# mainodzysk2.net
KiCad netlist of a schematic drawn in EAGLE
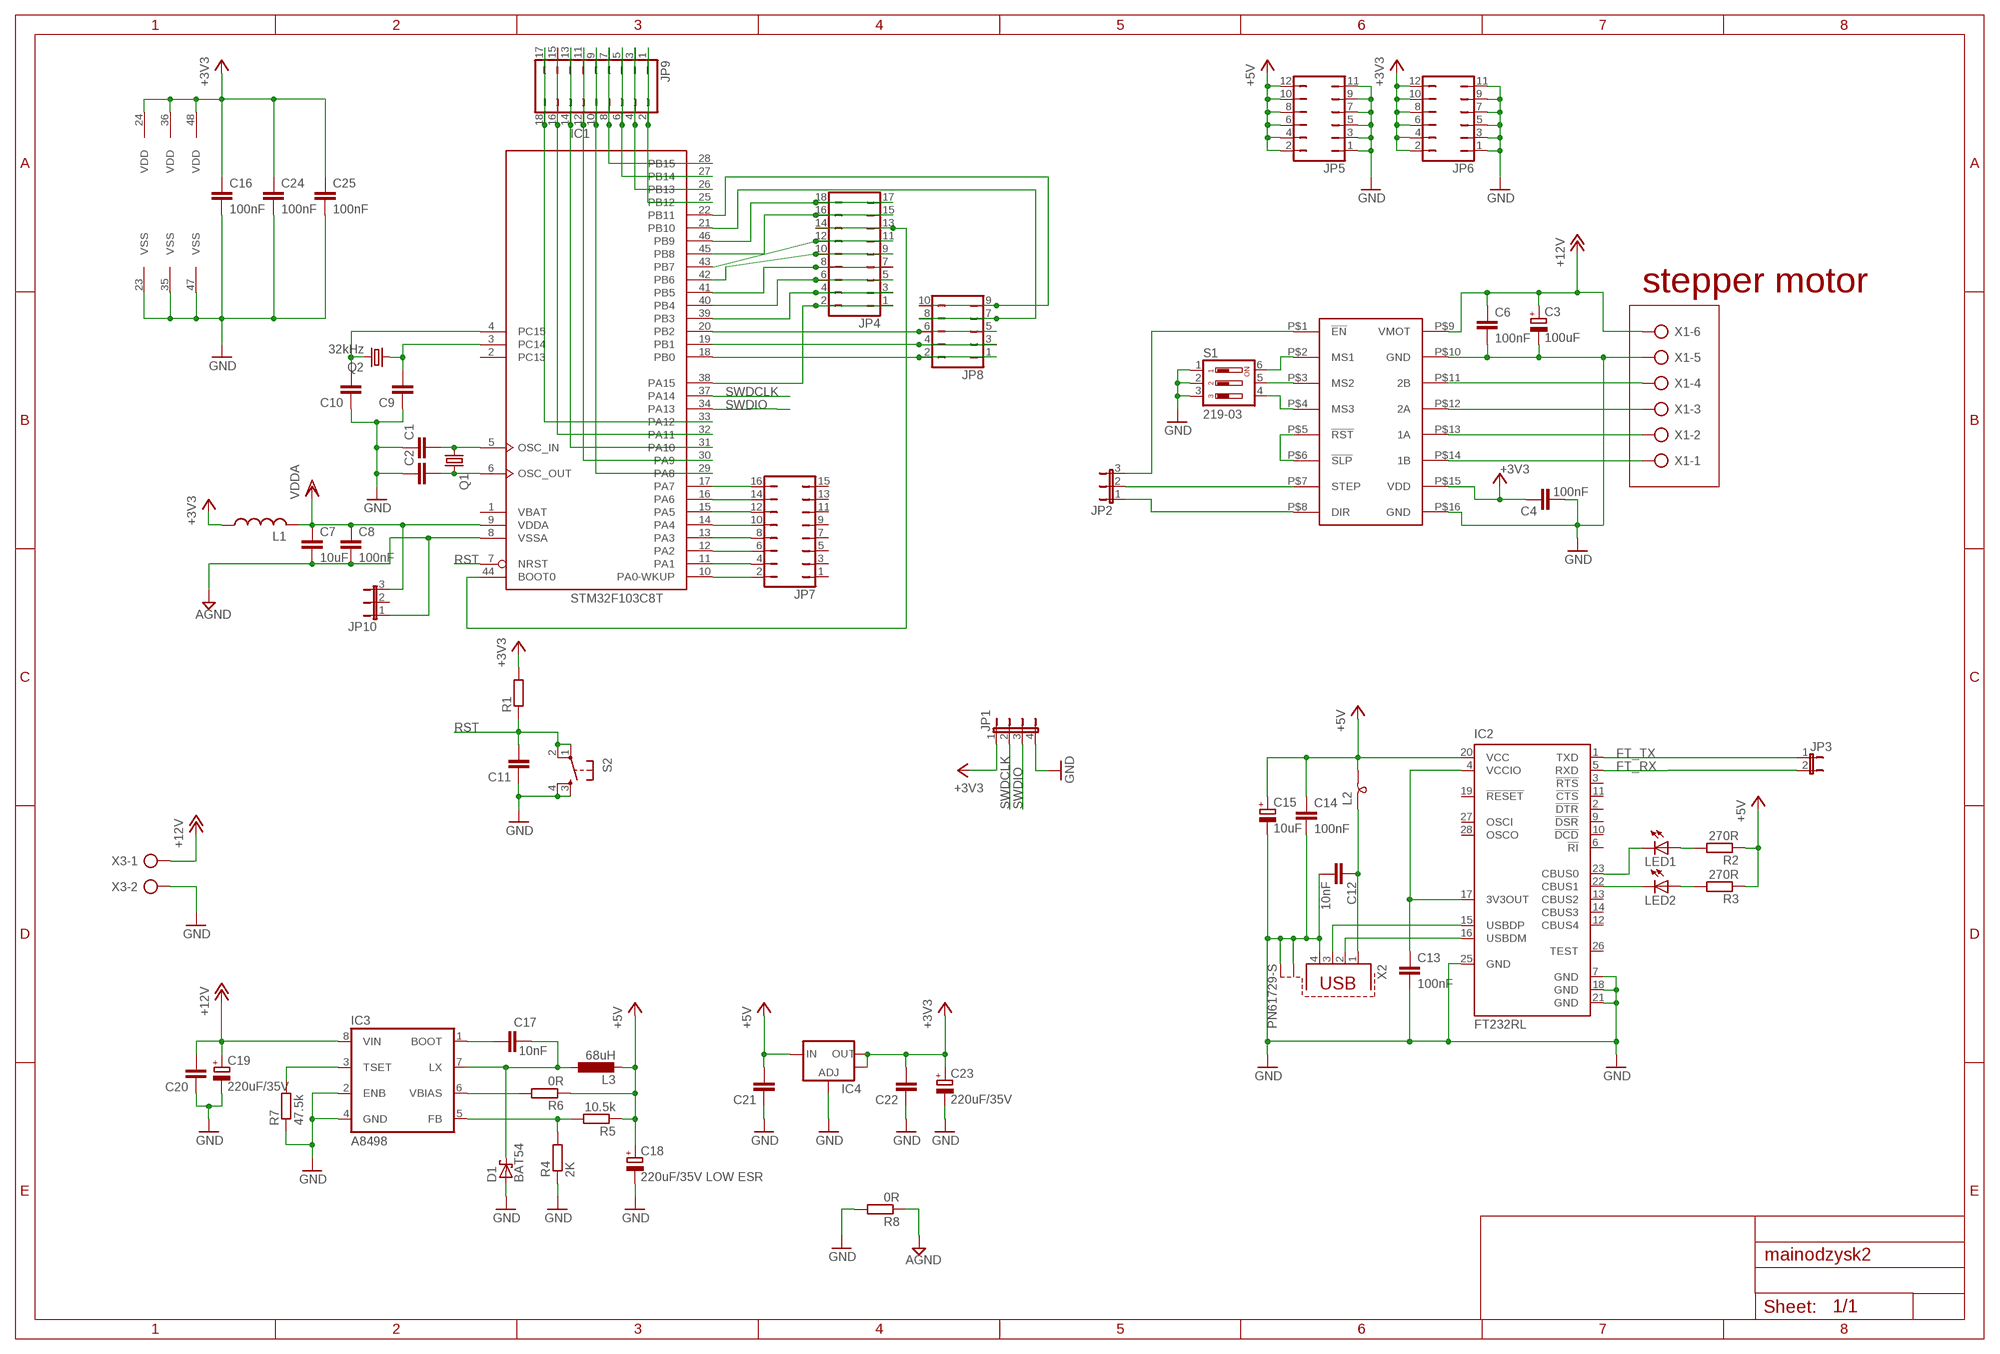
[diagram p0: schematic, sheet 1]

(export (version "E")
  (design (tool "Eeschema 10.0.6"))
  (components
    (comp (ref "C1")
      (value "C-EUC0603K")
      (footprint "eagle-import:C0603K")
      (libsource (lib "eagle-import") (part "C-EUC0603K"))
    )
    (comp (ref "C2")
      (value "C-EUC0603K")
      (footprint "eagle-import:C0603K")
      (libsource (lib "eagle-import") (part "C-EUC0603K"))
    )
    (comp (ref "C3")
      (value "100uF")
      (footprint "eagle-import:E5-10,5")
      (libsource (lib "eagle-import") (part "CPOL-EUE5-10.5"))
    )
    (comp (ref "C4")
      (value "100nF")
      (footprint "eagle-import:C0603K")
      (libsource (lib "eagle-import") (part "C-EUC0603K"))
    )
    (comp (ref "C6")
      (value "100nF")
      (footprint "eagle-import:C0603K")
      (libsource (lib "eagle-import") (part "C-EUC0603K"))
    )
    (comp (ref "C7")
      (value "10uF")
      (footprint "eagle-import:C1812")
      (libsource (lib "eagle-import") (part "C-EUC1812"))
    )
    (comp (ref "C8")
      (value "100nF")
      (footprint "eagle-import:C0603K")
      (libsource (lib "eagle-import") (part "C-EUC0603K"))
    )
    (comp (ref "C9")
      (value "C-EUC0603K")
      (footprint "eagle-import:C0603K")
      (libsource (lib "eagle-import") (part "C-EUC0603K"))
    )
    (comp (ref "C10")
      (value "C-EUC0603K")
      (footprint "eagle-import:C0603K")
      (libsource (lib "eagle-import") (part "C-EUC0603K"))
    )
    (comp (ref "C11")
      (value "C-EUC0603K")
      (footprint "eagle-import:C0603K")
      (libsource (lib "eagle-import") (part "C-EUC0603K"))
    )
    (comp (ref "C12")
      (value "10nF")
      (footprint "eagle-import:C0603K")
      (libsource (lib "eagle-import") (part "C-EUC0603K"))
    )
    (comp (ref "C13")
      (value "100nF")
      (footprint "eagle-import:C0603K")
      (libsource (lib "eagle-import") (part "C-EUC0603K"))
    )
    (comp (ref "C14")
      (value "100nF")
      (footprint "eagle-import:C0603K")
      (libsource (lib "eagle-import") (part "C-EUC0603K"))
    )
    (comp (ref "C15")
      (value "10uF")
      (footprint "eagle-import:E5-10,5")
      (libsource (lib "eagle-import") (part "CPOL-EUE5-10.5"))
    )
    (comp (ref "C16")
      (value "100nF")
      (footprint "eagle-import:C025-025X050")
      (libsource (lib "eagle-import") (part "C-EU025-025X050"))
    )
    (comp (ref "C17")
      (value "10nF")
      (footprint "eagle-import:C050-030X075")
      (libsource (lib "eagle-import") (part "C-EU050-030X075"))
    )
    (comp (ref "C18")
      (value "220uF/35V LOW ESR")
      (footprint "eagle-import:E5-10,5")
      (libsource (lib "eagle-import") (part "CPOL-EUE5-10.5"))
    )
    (comp (ref "C19")
      (value "220uF/35V")
      (footprint "eagle-import:E5-10,5")
      (libsource (lib "eagle-import") (part "CPOL-EUE5-10.5"))
    )
    (comp (ref "C20")
      (value "C-EUC0603K")
      (footprint "eagle-import:C0603K")
      (libsource (lib "eagle-import") (part "C-EUC0603K"))
    )
    (comp (ref "C21")
      (value "C-EUC0603K")
      (footprint "eagle-import:C0603K")
      (libsource (lib "eagle-import") (part "C-EUC0603K"))
    )
    (comp (ref "C22")
      (value "C-EUC0603K")
      (footprint "eagle-import:C0603K")
      (libsource (lib "eagle-import") (part "C-EUC0603K"))
    )
    (comp (ref "C23")
      (value "220uF/35V")
      (footprint "eagle-import:E5-10,5")
      (libsource (lib "eagle-import") (part "CPOL-EUE5-10.5"))
    )
    (comp (ref "C24")
      (value "100nF")
      (footprint "eagle-import:C0603K")
      (libsource (lib "eagle-import") (part "C-EUC0603K"))
    )
    (comp (ref "C25")
      (value "100nF")
      (footprint "eagle-import:C025-024X044")
      (libsource (lib "eagle-import") (part "C-EU025-024X044"))
    )
    (comp (ref "D1")
      (value "BAT54")
      (footprint "eagle-import:SOT23")
      (libsource (lib "eagle-import") (part "BAT54"))
    )
    (comp (ref "IC1")
      (value "STM32F103C8T")
      (footprint "eagle-import:LQFP48")
      (libsource (lib "eagle-import") (part "STM32F103CT8"))
    )
    (comp (ref "IC2")
      (value "FT232RL")
      (footprint "eagle-import:SSOP28")
      (libsource (lib "eagle-import") (part "FT232RL"))
    )
    (comp (ref "IC3")
      (value "A8498")
      (footprint "eagle-import:SO08")
      (libsource (lib "eagle-import") (part "A8498"))
    )
    (comp (ref "IC4")
      (value "V_REG_LM1117SOT223")
      (footprint "eagle-import:SOT223")
      (libsource (lib "eagle-import") (part "V_REG_LM1117SOT223"))
    )
    (comp (ref "JP1")
      (value "JP4E")
      (footprint "eagle-import:JP4")
      (libsource (lib "eagle-import") (part "JP4E"))
    )
    (comp (ref "JP2")
      (value "JP2E")
      (footprint "eagle-import:JP2")
      (libsource (lib "eagle-import") (part "JP2E"))
    )
    (comp (ref "JP3")
      (value "JP1E")
      (footprint "eagle-import:JP1")
      (libsource (lib "eagle-import") (part "JP1E"))
    )
    (comp (ref "JP4")
      (value "JP9Q")
      (footprint "eagle-import:JP9Q")
      (libsource (lib "eagle-import") (part "JP9Q"))
    )
    (comp (ref "JP5")
      (value "JP6Q")
      (footprint "eagle-import:JP6Q")
      (libsource (lib "eagle-import") (part "JP6Q"))
    )
    (comp (ref "JP6")
      (value "JP6Q")
      (footprint "eagle-import:JP6Q")
      (libsource (lib "eagle-import") (part "JP6Q"))
    )
    (comp (ref "JP7")
      (value "JP8Q")
      (footprint "eagle-import:JP8Q")
      (libsource (lib "eagle-import") (part "JP8Q"))
    )
    (comp (ref "JP8")
      (value "JP5Q")
      (footprint "eagle-import:JP5Q")
      (libsource (lib "eagle-import") (part "JP5Q"))
    )
    (comp (ref "JP9")
      (value "JP9Q")
      (footprint "eagle-import:JP9Q")
      (libsource (lib "eagle-import") (part "JP9Q"))
    )
    (comp (ref "JP10")
      (value "JP2W")
      (footprint "eagle-import:JP2W")
      (libsource (lib "eagle-import") (part "JP2W"))
    )
    (comp (ref "L1")
      (value "L-USL2012C")
      (footprint "eagle-import:L2012C")
      (libsource (lib "eagle-import") (part "L-USL2012C"))
    )
    (comp (ref "L2")
      (value "SM-B5")
      (footprint "eagle-import:SM-B5")
      (libsource (lib "eagle-import") (part "SM-B5"))
    )
    (comp (ref "L3")
      (value "68uH")
      (footprint "eagle-import:PIS2816")
      (libsource (lib "eagle-import") (part "L-EUPIS2816"))
    )
    (comp (ref "LED1")
      (value "LEDCHIPLED_0805")
      (footprint "eagle-import:CHIPLED_0805")
      (libsource (lib "eagle-import") (part "LEDCHIPLED_0805"))
    )
    (comp (ref "LED2")
      (value "LEDCHIPLED_0805")
      (footprint "eagle-import:CHIPLED_0805")
      (libsource (lib "eagle-import") (part "LEDCHIPLED_0805"))
    )
    (comp (ref "Q1")
      (value "CRYSTALHC49UP")
      (footprint "eagle-import:HC49UP")
      (libsource (lib "eagle-import") (part "CRYSTALHC49UP"))
    )
    (comp (ref "Q2")
      (value "32kHz")
      (footprint "eagle-import:TC26H")
      (libsource (lib "eagle-import") (part "CRYSTALTC26H"))
    )
    (comp (ref "R1")
      (value "R-EU_R0805")
      (footprint "eagle-import:R0805")
      (libsource (lib "eagle-import") (part "R-EU_R0805"))
    )
    (comp (ref "R2")
      (value "270R")
      (footprint "eagle-import:R0805")
      (libsource (lib "eagle-import") (part "R-EU_R0805"))
    )
    (comp (ref "R3")
      (value "270R")
      (footprint "eagle-import:R0805")
      (libsource (lib "eagle-import") (part "R-EU_R0805"))
    )
    (comp (ref "R4")
      (value "2K")
      (footprint "eagle-import:0207_12")
      (libsource (lib "eagle-import") (part "R-EU_0207/12"))
    )
    (comp (ref "R5")
      (value "10.5k")
      (footprint "eagle-import:R0805")
      (libsource (lib "eagle-import") (part "R-EU_R0805"))
    )
    (comp (ref "R6")
      (value "0R")
      (footprint "eagle-import:R0805")
      (libsource (lib "eagle-import") (part "R-EU_R0805"))
    )
    (comp (ref "R7")
      (value "47.5k")
      (footprint "eagle-import:R0805")
      (libsource (lib "eagle-import") (part "R-EU_R0805"))
    )
    (comp (ref "R8")
      (value "0R")
      (footprint "eagle-import:0207_10")
      (libsource (lib "eagle-import") (part "R-EU_0207/10"))
    )
    (comp (ref "S1")
      (value "219-03")
      (footprint "eagle-import:CTS-219-03")
      (libsource (lib "eagle-import") (part "219-03"))
    )
    (comp (ref "S2")
      (value "TAC_SWITCHPTH")
      (footprint "eagle-import:TACTILE-PTH")
      (libsource (lib "eagle-import") (part "TAC_SWITCHPTH"))
    )
    (comp (ref "U$1")
      (value "A4988_POLOLU_STEPER_MOTOR")
      (footprint "eagle-import:6X8")
      (libsource (lib "eagle-import") (part "A4988_POLOLU_STEPER_MOTOR"))
    )
    (comp (ref "X1")
      (value "AK300/6")
      (footprint "eagle-import:AK300_6")
      (libsource (lib "eagle-import") (part "AK300/6"))
    )
    (comp (ref "X2")
      (value "PN61729-S")
      (footprint "eagle-import:PN61729-S")
      (libsource (lib "eagle-import") (part "PN61729-S"))
    )
    (comp (ref "X3")
      (value "AK300/2")
      (footprint "eagle-import:AK300_2")
      (libsource (lib "eagle-import") (part "AK300/2"))
    )
  )
  (nets
    (net (code "1") (name "+3V3") (class "Default")
      (node (ref "C16") (pin "1") (pinfunction "1_1") (pintype "passive"))
      (node (ref "C22") (pin "2") (pinfunction "2_2") (pintype "passive"))
      (node (ref "C23") (pin "+") (pinfunction "+_+") (pintype "passive"))
      (node (ref "C24") (pin "1") (pinfunction "1_1") (pintype "passive"))
      (node (ref "C25") (pin "1") (pinfunction "1_1") (pintype "passive"))
      (node (ref "C4") (pin "1") (pinfunction "1_1") (pintype "passive"))
      (node (ref "IC1") (pin "24") (pinfunction "VDD_24") (pintype "power_in"))
      (node (ref "IC1") (pin "36") (pinfunction "VDD_36") (pintype "power_in"))
      (node (ref "IC1") (pin "48") (pinfunction "VDD_48") (pintype "power_in"))
      (node (ref "IC4") (pin "2") (pinfunction "OUT_2") (pintype "output"))
      (node (ref "IC4") (pin "4") (pinfunction "OUT_4") (pintype "output"))
      (node (ref "JP1") (pin "1") (pinfunction "1_1") (pintype "passive"))
      (node (ref "JP6") (pin "10") (pinfunction "10_10") (pintype "passive"))
      (node (ref "JP6") (pin "12") (pinfunction "12_12") (pintype "passive"))
      (node (ref "JP6") (pin "2") (pinfunction "2_2") (pintype "passive"))
      (node (ref "JP6") (pin "4") (pinfunction "4_4") (pintype "passive"))
      (node (ref "JP6") (pin "6") (pinfunction "6_6") (pintype "passive"))
      (node (ref "JP6") (pin "8") (pinfunction "8_8") (pintype "passive"))
      (node (ref "L1") (pin "1") (pinfunction "1_1") (pintype "passive"))
      (node (ref "R1") (pin "2") (pinfunction "2_2") (pintype "passive"))
      (node (ref "U$1") (pin "P$15") (pinfunction "VDD_P$15") (pintype "bidirectional"))
    )
    (net (code "2") (name "+5V") (class "Default")
      (node (ref "C14") (pin "1") (pinfunction "1_1") (pintype "passive"))
      (node (ref "C15") (pin "+") (pinfunction "+_+") (pintype "passive"))
      (node (ref "C18") (pin "+") (pinfunction "+_+") (pintype "passive"))
      (node (ref "C21") (pin "2") (pinfunction "2_2") (pintype "passive"))
      (node (ref "IC2") (pin "20") (pinfunction "VCC_20") (pintype "power_in"))
      (node (ref "IC4") (pin "3") (pinfunction "IN_3") (pintype "input"))
      (node (ref "JP5") (pin "10") (pinfunction "10_10") (pintype "passive"))
      (node (ref "JP5") (pin "12") (pinfunction "12_12") (pintype "passive"))
      (node (ref "JP5") (pin "2") (pinfunction "2_2") (pintype "passive"))
      (node (ref "JP5") (pin "4") (pinfunction "4_4") (pintype "passive"))
      (node (ref "JP5") (pin "6") (pinfunction "6_6") (pintype "passive"))
      (node (ref "JP5") (pin "8") (pinfunction "8_8") (pintype "passive"))
      (node (ref "L2") (pin "2") (pinfunction "2_2") (pintype "passive"))
      (node (ref "L3") (pin "2") (pinfunction "2_2") (pintype "passive"))
      (node (ref "R2") (pin "1") (pinfunction "1_1") (pintype "passive"))
      (node (ref "R3") (pin "1") (pinfunction "1_1") (pintype "passive"))
      (node (ref "R5") (pin "1") (pinfunction "1_1") (pintype "passive"))
      (node (ref "R6") (pin "1") (pinfunction "1_1") (pintype "passive"))
    )
    (net (code "3") (name "+12V") (class "Default")
      (node (ref "C19") (pin "+") (pinfunction "+_+") (pintype "passive"))
      (node (ref "C20") (pin "2") (pinfunction "2_2") (pintype "passive"))
      (node (ref "C3") (pin "+") (pinfunction "+_+") (pintype "passive"))
      (node (ref "C6") (pin "1") (pinfunction "1_1") (pintype "passive"))
      (node (ref "IC3") (pin "8") (pinfunction "VIN_8") (pintype "input"))
      (node (ref "U$1") (pin "P$9") (pinfunction "VMOT_P$9") (pintype "bidirectional"))
      (node (ref "X1") (pin "6") (pinfunction "KL_6") (pintype "passive"))
      (node (ref "X3") (pin "1") (pinfunction "KL_1") (pintype "passive"))
    )
    (net (code "4") (name "/FT_RX") (class "Default")
      (node (ref "IC2") (pin "5") (pinfunction "RXD_5") (pintype "input"))
      (node (ref "JP3") (pin "2") (pinfunction "2_2") (pintype "passive"))
    )
    (net (code "5") (name "/FT_TX") (class "Default")
      (node (ref "IC2") (pin "1") (pinfunction "TXD_1") (pintype "output"))
      (node (ref "JP3") (pin "1") (pinfunction "1_1") (pintype "passive"))
    )
    (net (code "6") (name "/RST") (class "Default")
      (node (ref "C11") (pin "2") (pinfunction "2_2") (pintype "passive"))
      (node (ref "IC1") (pin "7") (pinfunction "NRST_7") (pintype "bidirectional"))
      (node (ref "R1") (pin "1") (pinfunction "1_1") (pintype "passive"))
      (node (ref "S2") (pin "1") (pinfunction "1_1") (pintype "passive"))
      (node (ref "S2") (pin "2") (pinfunction "2_2") (pintype "passive"))
    )
    (net (code "7") (name "/SWDCLK") (class "Default")
      (node (ref "IC1") (pin "37") (pinfunction "PA14_37") (pintype "bidirectional"))
      (node (ref "JP1") (pin "2") (pinfunction "2_2") (pintype "passive"))
    )
    (net (code "8") (name "/SWDIO") (class "Default")
      (node (ref "IC1") (pin "34") (pinfunction "PA13_34") (pintype "bidirectional"))
      (node (ref "JP1") (pin "3") (pinfunction "3_3") (pintype "passive"))
    )
    (net (code "9") (name "/VBAT") (class "Default")
      (node (ref "IC1") (pin "1") (pinfunction "VBAT_1") (pintype "power_in"))
    )
    (net (code "10") (name "AGND") (class "Default")
      (node (ref "C7") (pin "2") (pinfunction "2_2") (pintype "passive"))
      (node (ref "C8") (pin "2") (pinfunction "2_2") (pintype "passive"))
      (node (ref "IC1") (pin "8") (pinfunction "VSSA_8") (pintype "power_in"))
      (node (ref "JP10") (pin "1") (pinfunction "1_1") (pintype "passive"))
      (node (ref "R8") (pin "1") (pinfunction "1_1") (pintype "passive"))
    )
    (net (code "11") (name "GND") (class "Default")
      (node (ref "C1") (pin "1") (pinfunction "1_1") (pintype "passive"))
      (node (ref "C10") (pin "1") (pinfunction "1_1") (pintype "passive"))
      (node (ref "C11") (pin "1") (pinfunction "1_1") (pintype "passive"))
      (node (ref "C12") (pin "2") (pinfunction "2_2") (pintype "passive"))
      (node (ref "C13") (pin "2") (pinfunction "2_2") (pintype "passive"))
      (node (ref "C14") (pin "2") (pinfunction "2_2") (pintype "passive"))
      (node (ref "C15") (pin "-") (pinfunction "-_-") (pintype "passive"))
      (node (ref "C16") (pin "2") (pinfunction "2_2") (pintype "passive"))
      (node (ref "C18") (pin "-") (pinfunction "-_-") (pintype "passive"))
      (node (ref "C19") (pin "-") (pinfunction "-_-") (pintype "passive"))
      (node (ref "C2") (pin "1") (pinfunction "1_1") (pintype "passive"))
      (node (ref "C20") (pin "1") (pinfunction "1_1") (pintype "passive"))
      (node (ref "C21") (pin "1") (pinfunction "1_1") (pintype "passive"))
      (node (ref "C22") (pin "1") (pinfunction "1_1") (pintype "passive"))
      (node (ref "C23") (pin "-") (pinfunction "-_-") (pintype "passive"))
      (node (ref "C24") (pin "2") (pinfunction "2_2") (pintype "passive"))
      (node (ref "C25") (pin "2") (pinfunction "2_2") (pintype "passive"))
      (node (ref "C3") (pin "-") (pinfunction "-_-") (pintype "passive"))
      (node (ref "C4") (pin "2") (pinfunction "2_2") (pintype "passive"))
      (node (ref "C6") (pin "2") (pinfunction "2_2") (pintype "passive"))
      (node (ref "C9") (pin "1") (pinfunction "1_1") (pintype "passive"))
      (node (ref "D1") (pin "1") (pinfunction "A_1") (pintype "passive"))
      (node (ref "IC1") (pin "23") (pinfunction "VSS_23") (pintype "power_in"))
      (node (ref "IC1") (pin "35") (pinfunction "VSS_35") (pintype "power_in"))
      (node (ref "IC1") (pin "47") (pinfunction "VSS_47") (pintype "power_in"))
      (node (ref "IC2") (pin "18") (pinfunction "GND_18") (pintype "power_in"))
      (node (ref "IC2") (pin "21") (pinfunction "GND_21") (pintype "power_in"))
      (node (ref "IC2") (pin "25") (pinfunction "GND_25") (pintype "power_in"))
      (node (ref "IC2") (pin "7") (pinfunction "GND_7") (pintype "power_in"))
      (node (ref "IC3") (pin "2") (pinfunction "ENB_2") (pintype "input"))
      (node (ref "IC3") (pin "4") (pinfunction "GND_4") (pintype "power_in"))
      (node (ref "IC4") (pin "1") (pinfunction "ADJ_1") (pintype "input"))
      (node (ref "JP1") (pin "4") (pinfunction "4_4") (pintype "passive"))
      (node (ref "JP5") (pin "1") (pinfunction "1_1") (pintype "passive"))
      (node (ref "JP5") (pin "11") (pinfunction "11_11") (pintype "passive"))
      (node (ref "JP5") (pin "3") (pinfunction "3_3") (pintype "passive"))
      (node (ref "JP5") (pin "5") (pinfunction "5_5") (pintype "passive"))
      (node (ref "JP5") (pin "7") (pinfunction "7_7") (pintype "passive"))
      (node (ref "JP5") (pin "9") (pinfunction "9_9") (pintype "passive"))
      (node (ref "JP6") (pin "1") (pinfunction "1_1") (pintype "passive"))
      (node (ref "JP6") (pin "11") (pinfunction "11_11") (pintype "passive"))
      (node (ref "JP6") (pin "3") (pinfunction "3_3") (pintype "passive"))
      (node (ref "JP6") (pin "5") (pinfunction "5_5") (pintype "passive"))
      (node (ref "JP6") (pin "7") (pinfunction "7_7") (pintype "passive"))
      (node (ref "JP6") (pin "9") (pinfunction "9_9") (pintype "passive"))
      (node (ref "R4") (pin "1") (pinfunction "1_1") (pintype "passive"))
      (node (ref "R7") (pin "1") (pinfunction "1_1") (pintype "passive"))
      (node (ref "R8") (pin "2") (pinfunction "2_2") (pintype "passive"))
      (node (ref "S1") (pin "1") (pinfunction "1_1") (pintype "passive"))
      (node (ref "S1") (pin "2") (pinfunction "2_2") (pintype "passive"))
      (node (ref "S1") (pin "3") (pinfunction "3_3") (pintype "passive"))
      (node (ref "S2") (pin "3") (pinfunction "3_3") (pintype "passive"))
      (node (ref "S2") (pin "4") (pinfunction "4_4") (pintype "passive"))
      (node (ref "U$1") (pin "P$10") (pinfunction "GND_P$10") (pintype "bidirectional"))
      (node (ref "U$1") (pin "P$16") (pinfunction "GND_P$16") (pintype "bidirectional"))
      (node (ref "X1") (pin "5") (pinfunction "KL_5") (pintype "passive"))
      (node (ref "X2") (pin "4") (pinfunction "4_4") (pintype "passive"))
      (node (ref "X2") (pin "S1") (pinfunction "S1_S1") (pintype "passive"))
      (node (ref "X2") (pin "S2") (pinfunction "S2_S2") (pintype "passive"))
      (node (ref "X3") (pin "2") (pinfunction "KL_2") (pintype "passive"))
    )
    (net (code "12") (name "Net-(C12-Pad1)") (class "Default")
      (node (ref "C12") (pin "1") (pinfunction "1_1") (pintype "passive"))
      (node (ref "L2") (pin "1") (pinfunction "1_1") (pintype "passive"))
      (node (ref "X2") (pin "1") (pinfunction "1_1") (pintype "passive"))
    )
    (net (code "13") (name "Net-(D1-C)") (class "Default")
      (node (ref "C17") (pin "1") (pinfunction "1_1") (pintype "passive"))
      (node (ref "D1") (pin "3") (pinfunction "C_3") (pintype "passive"))
      (node (ref "IC3") (pin "7") (pinfunction "LX_7") (pintype "input"))
      (node (ref "L3") (pin "1") (pinfunction "1_1") (pintype "passive"))
    )
    (net (code "14") (name "Net-(IC1A-BOOT0)") (class "Default")
      (node (ref "IC1") (pin "44") (pinfunction "BOOT0_44") (pintype "input"))
      (node (ref "JP4") (pin "13") (pinfunction "13_13") (pintype "passive"))
      (node (ref "JP4") (pin "14") (pinfunction "14_14") (pintype "passive"))
    )
    (net (code "15") (name "Net-(IC1A-OSC_IN)") (class "Default")
      (node (ref "C1") (pin "2") (pinfunction "2_2") (pintype "passive"))
      (node (ref "IC1") (pin "5") (pinfunction "OSC_IN_5") (pintype "bidirectional"))
      (node (ref "Q1") (pin "1") (pinfunction "1_1") (pintype "passive"))
    )
    (net (code "16") (name "Net-(IC1A-OSC_OUT)") (class "Default")
      (node (ref "C2") (pin "2") (pinfunction "2_2") (pintype "passive"))
      (node (ref "IC1") (pin "6") (pinfunction "OSC_OUT_6") (pintype "bidirectional"))
      (node (ref "Q1") (pin "2") (pinfunction "2_2") (pintype "passive"))
    )
    (net (code "17") (name "Net-(IC1A-PA0-WKUP)") (class "Default")
      (node (ref "IC1") (pin "10") (pinfunction "PA0-WKUP_10") (pintype "bidirectional"))
      (node (ref "JP7") (pin "2") (pinfunction "2_2") (pintype "passive"))
    )
    (net (code "18") (name "Net-(IC1A-PA1)") (class "Default")
      (node (ref "IC1") (pin "11") (pinfunction "PA1_11") (pintype "bidirectional"))
      (node (ref "JP7") (pin "4") (pinfunction "4_4") (pintype "passive"))
    )
    (net (code "19") (name "Net-(IC1A-PA2)") (class "Default")
      (node (ref "IC1") (pin "12") (pinfunction "PA2_12") (pintype "bidirectional"))
      (node (ref "JP7") (pin "6") (pinfunction "6_6") (pintype "passive"))
    )
    (net (code "20") (name "Net-(IC1A-PA3)") (class "Default")
      (node (ref "IC1") (pin "13") (pinfunction "PA3_13") (pintype "bidirectional"))
      (node (ref "JP7") (pin "8") (pinfunction "8_8") (pintype "passive"))
    )
    (net (code "21") (name "Net-(IC1A-PA4)") (class "Default")
      (node (ref "IC1") (pin "14") (pinfunction "PA4_14") (pintype "bidirectional"))
      (node (ref "JP7") (pin "10") (pinfunction "10_10") (pintype "passive"))
    )
    (net (code "22") (name "Net-(IC1A-PA5)") (class "Default")
      (node (ref "IC1") (pin "15") (pinfunction "PA5_15") (pintype "bidirectional"))
      (node (ref "JP7") (pin "12") (pinfunction "12_12") (pintype "passive"))
    )
    (net (code "23") (name "Net-(IC1A-PA6)") (class "Default")
      (node (ref "IC1") (pin "16") (pinfunction "PA6_16") (pintype "bidirectional"))
      (node (ref "JP7") (pin "14") (pinfunction "14_14") (pintype "passive"))
    )
    (net (code "24") (name "Net-(IC1A-PA7)") (class "Default")
      (node (ref "IC1") (pin "17") (pinfunction "PA7_17") (pintype "bidirectional"))
      (node (ref "JP7") (pin "16") (pinfunction "16_16") (pintype "passive"))
    )
    (net (code "25") (name "Net-(IC1A-PA8)") (class "Default")
      (node (ref "IC1") (pin "29") (pinfunction "PA8_29") (pintype "bidirectional"))
      (node (ref "JP9") (pin "10") (pinfunction "10_10") (pintype "passive"))
      (node (ref "JP9") (pin "9") (pinfunction "9_9") (pintype "passive"))
    )
    (net (code "26") (name "Net-(IC1A-PA9)") (class "Default")
      (node (ref "IC1") (pin "30") (pinfunction "PA9_30") (pintype "bidirectional"))
      (node (ref "JP9") (pin "11") (pinfunction "11_11") (pintype "passive"))
      (node (ref "JP9") (pin "12") (pinfunction "12_12") (pintype "passive"))
    )
    (net (code "27") (name "Net-(IC1A-PA10)") (class "Default")
      (node (ref "IC1") (pin "31") (pinfunction "PA10_31") (pintype "bidirectional"))
      (node (ref "JP9") (pin "13") (pinfunction "13_13") (pintype "passive"))
      (node (ref "JP9") (pin "14") (pinfunction "14_14") (pintype "passive"))
    )
    (net (code "28") (name "Net-(IC1A-PA11)") (class "Default")
      (node (ref "IC1") (pin "32") (pinfunction "PA11_32") (pintype "bidirectional"))
      (node (ref "JP9") (pin "15") (pinfunction "15_15") (pintype "passive"))
      (node (ref "JP9") (pin "16") (pinfunction "16_16") (pintype "passive"))
    )
    (net (code "29") (name "Net-(IC1A-PA12)") (class "Default")
      (node (ref "IC1") (pin "33") (pinfunction "PA12_33") (pintype "bidirectional"))
      (node (ref "JP9") (pin "17") (pinfunction "17_17") (pintype "passive"))
      (node (ref "JP9") (pin "18") (pinfunction "18_18") (pintype "passive"))
    )
    (net (code "30") (name "Net-(IC1A-PA15)") (class "Default")
      (node (ref "IC1") (pin "38") (pinfunction "PA15_38") (pintype "bidirectional"))
      (node (ref "JP4") (pin "1") (pinfunction "1_1") (pintype "passive"))
      (node (ref "JP4") (pin "2") (pinfunction "2_2") (pintype "passive"))
    )
    (net (code "31") (name "Net-(IC1A-PB0)") (class "Default")
      (node (ref "IC1") (pin "18") (pinfunction "PB0_18") (pintype "bidirectional"))
      (node (ref "JP8") (pin "1") (pinfunction "1_1") (pintype "passive"))
      (node (ref "JP8") (pin "2") (pinfunction "2_2") (pintype "passive"))
    )
    (net (code "32") (name "Net-(IC1A-PB1)") (class "Default")
      (node (ref "IC1") (pin "19") (pinfunction "PB1_19") (pintype "bidirectional"))
      (node (ref "JP8") (pin "3") (pinfunction "3_3") (pintype "passive"))
      (node (ref "JP8") (pin "4") (pinfunction "4_4") (pintype "passive"))
    )
    (net (code "33") (name "Net-(IC1A-PB2)") (class "Default")
      (node (ref "IC1") (pin "20") (pinfunction "PB2_20") (pintype "bidirectional"))
      (node (ref "JP8") (pin "5") (pinfunction "5_5") (pintype "passive"))
      (node (ref "JP8") (pin "6") (pinfunction "6_6") (pintype "passive"))
    )
    (net (code "34") (name "Net-(IC1A-PB3)") (class "Default")
      (node (ref "IC1") (pin "39") (pinfunction "PB3_39") (pintype "bidirectional"))
      (node (ref "JP4") (pin "3") (pinfunction "3_3") (pintype "passive"))
      (node (ref "JP4") (pin "4") (pinfunction "4_4") (pintype "passive"))
    )
    (net (code "35") (name "Net-(IC1A-PB4)") (class "Default")
      (node (ref "IC1") (pin "40") (pinfunction "PB4_40") (pintype "bidirectional"))
      (node (ref "JP4") (pin "5") (pinfunction "5_5") (pintype "passive"))
      (node (ref "JP4") (pin "6") (pinfunction "6_6") (pintype "passive"))
    )
    (net (code "36") (name "Net-(IC1A-PB5)") (class "Default")
      (node (ref "IC1") (pin "41") (pinfunction "PB5_41") (pintype "bidirectional"))
      (node (ref "JP4") (pin "7") (pinfunction "7_7") (pintype "passive"))
      (node (ref "JP4") (pin "8") (pinfunction "8_8") (pintype "passive"))
    )
    (net (code "37") (name "Net-(IC1A-PB6)") (class "Default")
      (node (ref "IC1") (pin "42") (pinfunction "PB6_42") (pintype "bidirectional"))
      (node (ref "JP4") (pin "10") (pinfunction "10_10") (pintype "passive"))
      (node (ref "JP4") (pin "9") (pinfunction "9_9") (pintype "passive"))
    )
    (net (code "38") (name "Net-(IC1A-PB7)") (class "Default")
      (node (ref "IC1") (pin "43") (pinfunction "PB7_43") (pintype "bidirectional"))
      (node (ref "JP4") (pin "11") (pinfunction "11_11") (pintype "passive"))
      (node (ref "JP4") (pin "12") (pinfunction "12_12") (pintype "passive"))
    )
    (net (code "39") (name "Net-(IC1A-PB8)") (class "Default")
      (node (ref "IC1") (pin "45") (pinfunction "PB8_45") (pintype "bidirectional"))
      (node (ref "JP4") (pin "15") (pinfunction "15_15") (pintype "passive"))
      (node (ref "JP4") (pin "16") (pinfunction "16_16") (pintype "passive"))
    )
    (net (code "40") (name "Net-(IC1A-PB9)") (class "Default")
      (node (ref "IC1") (pin "46") (pinfunction "PB9_46") (pintype "bidirectional"))
      (node (ref "JP4") (pin "17") (pinfunction "17_17") (pintype "passive"))
      (node (ref "JP4") (pin "18") (pinfunction "18_18") (pintype "passive"))
    )
    (net (code "41") (name "Net-(IC1A-PB10)") (class "Default")
      (node (ref "IC1") (pin "21") (pinfunction "PB10_21") (pintype "bidirectional"))
      (node (ref "JP8") (pin "7") (pinfunction "7_7") (pintype "passive"))
      (node (ref "JP8") (pin "8") (pinfunction "8_8") (pintype "passive"))
    )
    (net (code "42") (name "Net-(IC1A-PB11)") (class "Default")
      (node (ref "IC1") (pin "22") (pinfunction "PB11_22") (pintype "bidirectional"))
      (node (ref "JP8") (pin "10") (pinfunction "10_10") (pintype "passive"))
      (node (ref "JP8") (pin "9") (pinfunction "9_9") (pintype "passive"))
    )
    (net (code "43") (name "Net-(IC1A-PB12)") (class "Default")
      (node (ref "IC1") (pin "25") (pinfunction "PB12_25") (pintype "bidirectional"))
      (node (ref "JP9") (pin "1") (pinfunction "1_1") (pintype "passive"))
      (node (ref "JP9") (pin "2") (pinfunction "2_2") (pintype "passive"))
    )
    (net (code "44") (name "Net-(IC1A-PB13)") (class "Default")
      (node (ref "IC1") (pin "26") (pinfunction "PB13_26") (pintype "bidirectional"))
      (node (ref "JP9") (pin "3") (pinfunction "3_3") (pintype "passive"))
      (node (ref "JP9") (pin "4") (pinfunction "4_4") (pintype "passive"))
    )
    (net (code "45") (name "Net-(IC1A-PB14)") (class "Default")
      (node (ref "IC1") (pin "27") (pinfunction "PB14_27") (pintype "bidirectional"))
      (node (ref "JP9") (pin "5") (pinfunction "5_5") (pintype "passive"))
      (node (ref "JP9") (pin "6") (pinfunction "6_6") (pintype "passive"))
    )
    (net (code "46") (name "Net-(IC1A-PB15)") (class "Default")
      (node (ref "IC1") (pin "28") (pinfunction "PB15_28") (pintype "bidirectional"))
      (node (ref "JP9") (pin "7") (pinfunction "7_7") (pintype "passive"))
      (node (ref "JP9") (pin "8") (pinfunction "8_8") (pintype "passive"))
    )
    (net (code "47") (name "Net-(IC1A-PC14)") (class "Default")
      (node (ref "C9") (pin "2") (pinfunction "2_2") (pintype "passive"))
      (node (ref "IC1") (pin "3") (pinfunction "PC14_3") (pintype "bidirectional"))
      (node (ref "Q2") (pin "1") (pinfunction "1_1") (pintype "passive"))
    )
    (net (code "48") (name "Net-(IC1A-PC15)") (class "Default")
      (node (ref "C10") (pin "2") (pinfunction "2_2") (pintype "passive"))
      (node (ref "IC1") (pin "4") (pinfunction "PC15_4") (pintype "bidirectional"))
      (node (ref "Q2") (pin "2") (pinfunction "2_2") (pintype "passive"))
    )
    (net (code "49") (name "Net-(IC2-3V3OUT)") (class "Default")
      (node (ref "C13") (pin "1") (pinfunction "1_1") (pintype "passive"))
      (node (ref "IC2") (pin "17") (pinfunction "3V3OUT_17") (pintype "output"))
      (node (ref "IC2") (pin "4") (pinfunction "VCCIO_4") (pintype "power_in"))
    )
    (net (code "50") (name "Net-(IC2-CBUS0)") (class "Default")
      (node (ref "IC2") (pin "23") (pinfunction "CBUS0_23") (pintype "bidirectional"))
      (node (ref "LED1") (pin "C") (pinfunction "C_C") (pintype "passive"))
    )
    (net (code "51") (name "Net-(IC2-CBUS1)") (class "Default")
      (node (ref "IC2") (pin "22") (pinfunction "CBUS1_22") (pintype "bidirectional"))
      (node (ref "LED2") (pin "C") (pinfunction "C_C") (pintype "passive"))
    )
    (net (code "52") (name "Net-(IC2-USBDM)") (class "Default")
      (node (ref "IC2") (pin "16") (pinfunction "USBDM_16") (pintype "bidirectional"))
      (node (ref "X2") (pin "2") (pinfunction "2_2") (pintype "passive"))
    )
    (net (code "53") (name "Net-(IC2-USBDP)") (class "Default")
      (node (ref "IC2") (pin "15") (pinfunction "USBDP_15") (pintype "bidirectional"))
      (node (ref "X2") (pin "3") (pinfunction "3_3") (pintype "passive"))
    )
    (net (code "54") (name "Net-(IC3-BOOT)") (class "Default")
      (node (ref "C17") (pin "2") (pinfunction "2_2") (pintype "passive"))
      (node (ref "IC3") (pin "1") (pinfunction "BOOT_1") (pintype "output"))
    )
    (net (code "55") (name "Net-(IC3-FB)") (class "Default")
      (node (ref "IC3") (pin "5") (pinfunction "FB_5") (pintype "power_in"))
      (node (ref "R4") (pin "2") (pinfunction "2_2") (pintype "passive"))
      (node (ref "R5") (pin "2") (pinfunction "2_2") (pintype "passive"))
    )
    (net (code "56") (name "Net-(IC3-TSET)") (class "Default")
      (node (ref "IC3") (pin "3") (pinfunction "TSET_3") (pintype "input"))
      (node (ref "R7") (pin "2") (pinfunction "2_2") (pintype "passive"))
    )
    (net (code "57") (name "Net-(IC3-VBIAS)") (class "Default")
      (node (ref "IC3") (pin "6") (pinfunction "VBIAS_6") (pintype "input"))
      (node (ref "R6") (pin "2") (pinfunction "2_2") (pintype "passive"))
    )
    (net (code "58") (name "Net-(LED1-PadA)") (class "Default")
      (node (ref "LED1") (pin "A") (pinfunction "A_A") (pintype "passive"))
      (node (ref "R2") (pin "2") (pinfunction "2_2") (pintype "passive"))
    )
    (net (code "59") (name "Net-(LED2-PadA)") (class "Default")
      (node (ref "LED2") (pin "A") (pinfunction "A_A") (pintype "passive"))
      (node (ref "R3") (pin "2") (pinfunction "2_2") (pintype "passive"))
    )
    (net (code "60") (name "Net-(U$1-1A)") (class "Default")
      (node (ref "U$1") (pin "P$13") (pinfunction "1A_P$13") (pintype "bidirectional"))
      (node (ref "X1") (pin "2") (pinfunction "KL_2") (pintype "passive"))
    )
    (net (code "61") (name "Net-(U$1-1B)") (class "Default")
      (node (ref "U$1") (pin "P$14") (pinfunction "1B_P$14") (pintype "bidirectional"))
      (node (ref "X1") (pin "1") (pinfunction "KL_1") (pintype "passive"))
    )
    (net (code "62") (name "Net-(U$1-2A)") (class "Default")
      (node (ref "U$1") (pin "P$12") (pinfunction "2A_P$12") (pintype "bidirectional"))
      (node (ref "X1") (pin "3") (pinfunction "KL_3") (pintype "passive"))
    )
    (net (code "63") (name "Net-(U$1-2B)") (class "Default")
      (node (ref "U$1") (pin "P$11") (pinfunction "2B_P$11") (pintype "bidirectional"))
      (node (ref "X1") (pin "4") (pinfunction "KL_4") (pintype "passive"))
    )
    (net (code "64") (name "Net-(U$1-DIR)") (class "Default")
      (node (ref "JP2") (pin "1") (pinfunction "1_1") (pintype "passive"))
      (node (ref "U$1") (pin "P$8") (pinfunction "DIR_P$8") (pintype "bidirectional"))
    )
    (net (code "65") (name "Net-(U$1-MS1)") (class "Default")
      (node (ref "S1") (pin "6") (pinfunction "6_6") (pintype "passive"))
      (node (ref "U$1") (pin "P$2") (pinfunction "MS1_P$2") (pintype "bidirectional"))
    )
    (net (code "66") (name "Net-(U$1-MS2)") (class "Default")
      (node (ref "S1") (pin "5") (pinfunction "5_5") (pintype "passive"))
      (node (ref "U$1") (pin "P$3") (pinfunction "MS2_P$3") (pintype "bidirectional"))
    )
    (net (code "67") (name "Net-(U$1-MS3)") (class "Default")
      (node (ref "S1") (pin "4") (pinfunction "4_4") (pintype "passive"))
      (node (ref "U$1") (pin "P$4") (pinfunction "MS3_P$4") (pintype "bidirectional"))
    )
    (net (code "68") (name "Net-(U$1-STEP)") (class "Default")
      (node (ref "JP2") (pin "2") (pinfunction "2_2") (pintype "passive"))
      (node (ref "U$1") (pin "P$7") (pinfunction "STEP_P$7") (pintype "bidirectional"))
    )
    (net (code "69") (name "Net-(U$1-~{EN})") (class "Default")
      (node (ref "JP2") (pin "3") (pinfunction "3_3") (pintype "passive"))
      (node (ref "U$1") (pin "P$1") (pinfunction "~{EN}_P$1") (pintype "bidirectional"))
    )
    (net (code "70") (name "Net-(U$1-~{RST})") (class "Default")
      (node (ref "U$1") (pin "P$5") (pinfunction "~{RST}_P$5") (pintype "bidirectional"))
      (node (ref "U$1") (pin "P$6") (pinfunction "~{SLP}_P$6") (pintype "bidirectional"))
    )
    (net (code "71") (name "VDDA") (class "Default")
      (node (ref "C7") (pin "1") (pinfunction "1_1") (pintype "passive"))
      (node (ref "C8") (pin "1") (pinfunction "1_1") (pintype "passive"))
      (node (ref "IC1") (pin "9") (pinfunction "VDDA_9") (pintype "power_in"))
      (node (ref "JP10") (pin "3") (pinfunction "3_3") (pintype "passive"))
      (node (ref "L1") (pin "2") (pinfunction "2_2") (pintype "passive"))
    )
    (net (code "72") (name "unconnected-(IC1A-PC13-Pad2)") (class "Default")
      (node (ref "IC1") (pin "2") (pinfunction "PC13_2") (pintype "bidirectional"))
    )
    (net (code "73") (name "unconnected-(IC2-CBUS2-Pad13)") (class "Default")
      (node (ref "IC2") (pin "13") (pinfunction "CBUS2_13") (pintype "bidirectional"))
    )
    (net (code "74") (name "unconnected-(IC2-CBUS3-Pad14)") (class "Default")
      (node (ref "IC2") (pin "14") (pinfunction "CBUS3_14") (pintype "bidirectional"))
    )
    (net (code "75") (name "unconnected-(IC2-CBUS4-Pad12)") (class "Default")
      (node (ref "IC2") (pin "12") (pinfunction "CBUS4_12") (pintype "bidirectional"))
    )
    (net (code "76") (name "unconnected-(IC2-OSCI-Pad27)") (class "Default")
      (node (ref "IC2") (pin "27") (pinfunction "OSCI_27") (pintype "input"))
    )
    (net (code "77") (name "unconnected-(IC2-OSCO-Pad28)") (class "Default")
      (node (ref "IC2") (pin "28") (pinfunction "OSCO_28") (pintype "output"))
    )
    (net (code "78") (name "unconnected-(IC2-TEST-Pad26)") (class "Default")
      (node (ref "IC2") (pin "26") (pinfunction "TEST_26") (pintype "input"))
    )
    (net (code "79") (name "unconnected-(IC2-~{CTS}-Pad11)") (class "Default")
      (node (ref "IC2") (pin "11") (pinfunction "~{CTS}_11") (pintype "input"))
    )
    (net (code "80") (name "unconnected-(IC2-~{DCD}-Pad10)") (class "Default")
      (node (ref "IC2") (pin "10") (pinfunction "~{DCD}_10") (pintype "input"))
    )
    (net (code "81") (name "unconnected-(IC2-~{DSR}-Pad9)") (class "Default")
      (node (ref "IC2") (pin "9") (pinfunction "~{DSR}_9") (pintype "input"))
    )
    (net (code "82") (name "unconnected-(IC2-~{DTR}-Pad2)") (class "Default")
      (node (ref "IC2") (pin "2") (pinfunction "~{DTR}_2") (pintype "output"))
    )
    (net (code "83") (name "unconnected-(IC2-~{RESET}-Pad19)") (class "Default")
      (node (ref "IC2") (pin "19") (pinfunction "~{RESET}_19") (pintype "input"))
    )
    (net (code "84") (name "unconnected-(IC2-~{RI}-Pad6)") (class "Default")
      (node (ref "IC2") (pin "6") (pinfunction "~{RI}_6") (pintype "input"))
    )
    (net (code "85") (name "unconnected-(IC2-~{RTS}-Pad3)") (class "Default")
      (node (ref "IC2") (pin "3") (pinfunction "~{RTS}_3") (pintype "output"))
    )
    (net (code "86") (name "unconnected-(JP7-Pad1)") (class "Default")
      (node (ref "JP7") (pin "1") (pinfunction "1_1") (pintype "passive"))
    )
    (net (code "87") (name "unconnected-(JP7-Pad3)") (class "Default")
      (node (ref "JP7") (pin "3") (pinfunction "3_3") (pintype "passive"))
    )
    (net (code "88") (name "unconnected-(JP7-Pad5)") (class "Default")
      (node (ref "JP7") (pin "5") (pinfunction "5_5") (pintype "passive"))
    )
    (net (code "89") (name "unconnected-(JP7-Pad7)") (class "Default")
      (node (ref "JP7") (pin "7") (pinfunction "7_7") (pintype "passive"))
    )
    (net (code "90") (name "unconnected-(JP7-Pad9)") (class "Default")
      (node (ref "JP7") (pin "9") (pinfunction "9_9") (pintype "passive"))
    )
    (net (code "91") (name "unconnected-(JP7-Pad11)") (class "Default")
      (node (ref "JP7") (pin "11") (pinfunction "11_11") (pintype "passive"))
    )
    (net (code "92") (name "unconnected-(JP7-Pad13)") (class "Default")
      (node (ref "JP7") (pin "13") (pinfunction "13_13") (pintype "passive"))
    )
    (net (code "93") (name "unconnected-(JP7-Pad15)") (class "Default")
      (node (ref "JP7") (pin "15") (pinfunction "15_15") (pintype "passive"))
    )
    (net (code "94") (name "unconnected-(JP10-Pad2)") (class "Default")
      (node (ref "JP10") (pin "2") (pinfunction "2_2") (pintype "passive"))
    )
  )
)
